# FIT_HDMI_X34-28.net
KiCad netlist of a schematic drawn in Altium Designer
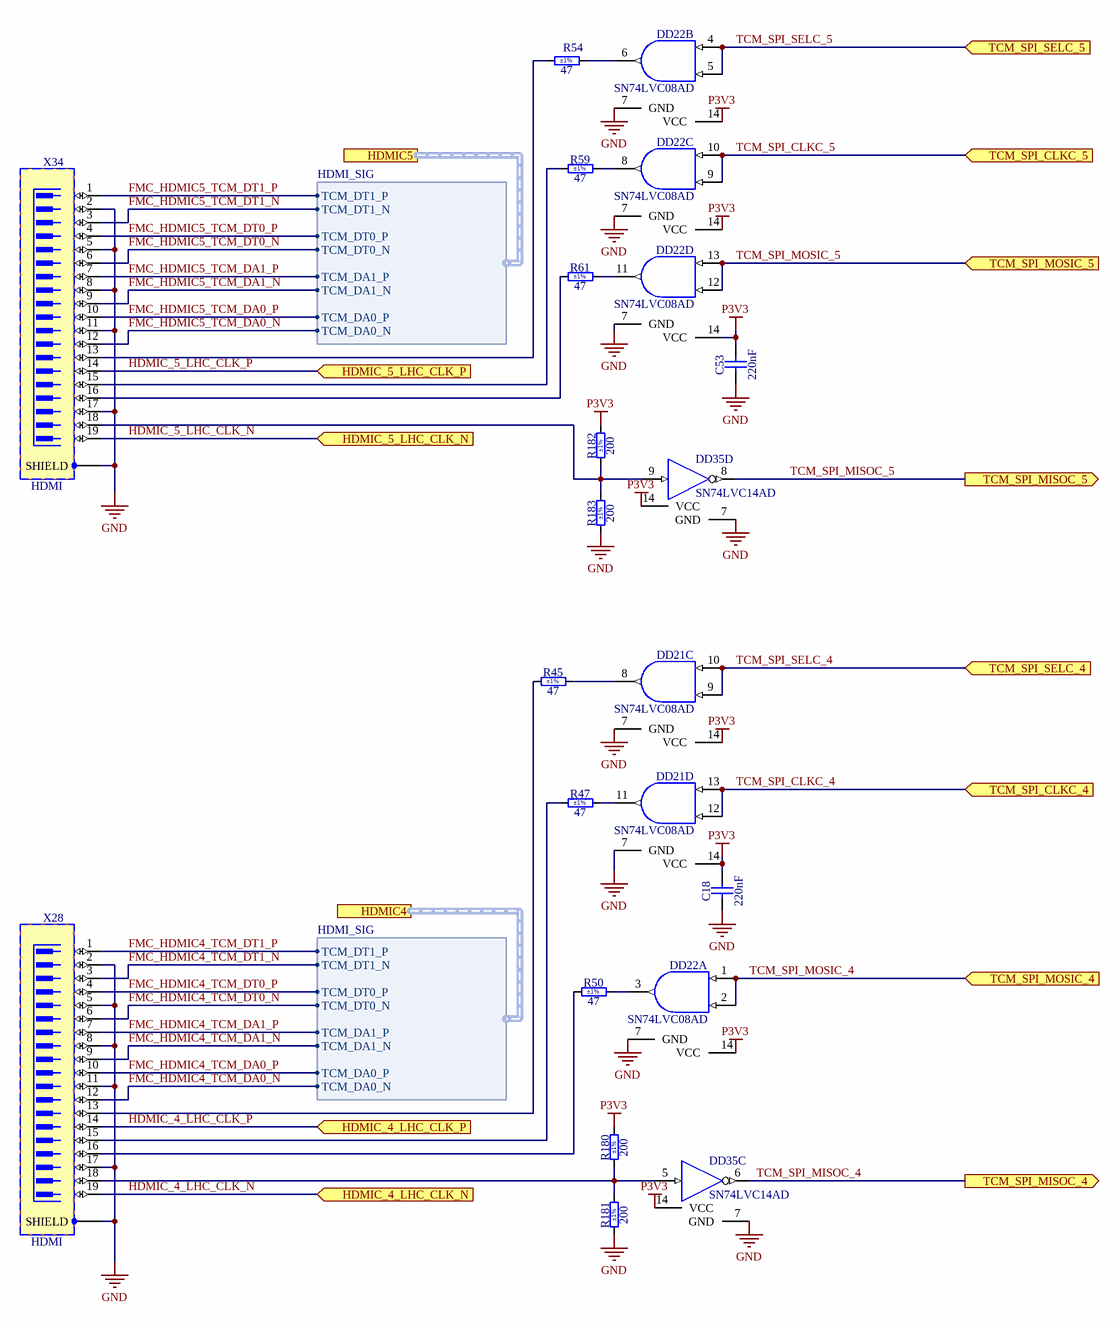
[diagram p0: FIT_HDMI_X34-28.SchDoc]

(export (version "E")
  (design (tool "Eeschema 10.0.6"))
  (components
    (comp (ref "C18")
      (value "220nF")
      (footprint "CAPC2012X135N")
      (description "Non-polarised capacitor")
      (fields
        (field (name "PART NUMBER") "CC0805_220NF_50V_10%_X7R")
        (field (name "VOLTAGE") "50V")
        (field (name "AUTHOR") "CERN DEM JLC")
      )
      (libsource (lib "Capacitors") (part "Capacitor - non polarized"))
    )
    (comp (ref "C53")
      (value "220nF")
      (footprint "CAPC2012X135N")
      (description "Non-polarised capacitor")
      (fields
        (field (name "PART NUMBER") "CC0805_220NF_50V_10%_X7R")
        (field (name "VOLTAGE") "50V")
        (field (name "AUTHOR") "CERN DEM JLC")
      )
      (libsource (lib "Capacitors") (part "Capacitor - non polarized"))
    )
    (comp (ref "DD21")
      (value "SN74LVC08AD")
      (footprint "SOIC127P600X175-14N")
      (description "Quad 2-Input AND Gate")
      (fields (field (name "MANUFACTURER") "TEXAS INSTRUMENTS") (field (name "AUTHOR") "CERN DEM JLC"))
      (libsource (lib "ICs And Semiconductors") (part "7408"))
    )
    (comp (ref "DD22")
      (value "SN74LVC08AD")
      (footprint "SOIC127P600X175-14N")
      (description "Quad 2-Input AND Gate")
      (fields (field (name "MANUFACTURER") "TEXAS INSTRUMENTS") (field (name "AUTHOR") "CERN DEM JLC"))
      (libsource (lib "ICs And Semiconductors") (part "7408"))
    )
    (comp (ref "DD35")
      (value "SN74LVC14AD")
      (footprint "SOIC127P600X175-14N")
      (description "Hex Schmitt-Trigger Inverter")
      (fields (field (name "MANUFACTURER") "TEXAS INSTRUMENTS") (field (name "AUTHOR") "CERN DEM JMW"))
      (libsource (lib "ICs And Semiconductors") (part "7414"))
    )
    (comp (ref "R45")
      (value "47")
      (footprint "RESC2012X60N")
      (description "Resistor - 1%")
      (fields
        (field (name "TOLERANCE") "±1%")
        (field (name "PART NUMBER") "R0805_47R_1%_0.125W_100PPM")
        (field (name "POWER") "0.125W")
        (field (name "AUTHOR") "CERN DEM JLC")
      )
      (libsource (lib "Resistors") (part "Resistor - 1%"))
    )
    (comp (ref "R47")
      (value "47")
      (footprint "RESC2012X60N")
      (description "Resistor - 1%")
      (fields
        (field (name "TOLERANCE") "±1%")
        (field (name "PART NUMBER") "R0805_47R_1%_0.125W_100PPM")
        (field (name "POWER") "0.125W")
        (field (name "AUTHOR") "CERN DEM JLC")
      )
      (libsource (lib "Resistors") (part "Resistor - 1%"))
    )
    (comp (ref "R50")
      (value "47")
      (footprint "RESC2012X60N")
      (description "Resistor - 1%")
      (fields
        (field (name "TOLERANCE") "±1%")
        (field (name "PART NUMBER") "R0805_47R_1%_0.125W_100PPM")
        (field (name "POWER") "0.125W")
        (field (name "AUTHOR") "CERN DEM JLC")
      )
      (libsource (lib "Resistors") (part "Resistor - 1%"))
    )
    (comp (ref "R54")
      (value "47")
      (footprint "RESC2012X60N")
      (description "Resistor - 1%")
      (fields
        (field (name "TOLERANCE") "±1%")
        (field (name "PART NUMBER") "R0805_47R_1%_0.125W_100PPM")
        (field (name "POWER") "0.125W")
        (field (name "AUTHOR") "CERN DEM JLC")
      )
      (libsource (lib "Resistors") (part "Resistor - 1%"))
    )
    (comp (ref "R59")
      (value "47")
      (footprint "RESC2012X60N")
      (description "Resistor - 1%")
      (fields
        (field (name "TOLERANCE") "±1%")
        (field (name "PART NUMBER") "R0805_47R_1%_0.125W_100PPM")
        (field (name "POWER") "0.125W")
        (field (name "AUTHOR") "CERN DEM JLC")
      )
      (libsource (lib "Resistors") (part "Resistor - 1%"))
    )
    (comp (ref "R61")
      (value "47")
      (footprint "RESC2012X60N")
      (description "Resistor - 1%")
      (fields
        (field (name "TOLERANCE") "±1%")
        (field (name "PART NUMBER") "R0805_47R_1%_0.125W_100PPM")
        (field (name "POWER") "0.125W")
        (field (name "AUTHOR") "CERN DEM JLC")
      )
      (libsource (lib "Resistors") (part "Resistor - 1%"))
    )
    (comp (ref "R180")
      (value "200")
      (footprint "RESC2012X60N")
      (description "Resistor - 1%")
      (fields
        (field (name "TOLERANCE") "±1%")
        (field (name "PART NUMBER") "R0805_200R_1%_0.125W_100PPM")
        (field (name "POWER") "0.125W")
        (field (name "AUTHOR") "CERN DEM JLC")
      )
      (libsource (lib "Resistors") (part "Resistor - 1%"))
    )
    (comp (ref "R181")
      (value "200")
      (footprint "RESC2012X60N")
      (description "Resistor - 1%")
      (fields
        (field (name "TOLERANCE") "±1%")
        (field (name "PART NUMBER") "R0805_200R_1%_0.125W_100PPM")
        (field (name "POWER") "0.125W")
        (field (name "AUTHOR") "CERN DEM JLC")
      )
      (libsource (lib "Resistors") (part "Resistor - 1%"))
    )
    (comp (ref "R182")
      (value "200")
      (footprint "RESC2012X60N")
      (description "Resistor - 1%")
      (fields
        (field (name "TOLERANCE") "±1%")
        (field (name "PART NUMBER") "R0805_200R_1%_0.125W_100PPM")
        (field (name "POWER") "0.125W")
        (field (name "AUTHOR") "CERN DEM JLC")
      )
      (libsource (lib "Resistors") (part "Resistor - 1%"))
    )
    (comp (ref "R183")
      (value "200")
      (footprint "RESC2012X60N")
      (description "Resistor - 1%")
      (fields
        (field (name "TOLERANCE") "±1%")
        (field (name "PART NUMBER") "R0805_200R_1%_0.125W_100PPM")
        (field (name "POWER") "0.125W")
        (field (name "AUTHOR") "CERN DEM JLC")
      )
      (libsource (lib "Resistors") (part "Resistor - 1%"))
    )
    (comp (ref "X28")
      (value "HDMI")
      (footprint "TYCO_2007435-1")
      (description "Connector HDMI 19 Male + 1 Shield")
      (fields
        (field (name "PART NUMBER") "TYCO_2007435-1")
        (field (name "MANUFACTURER") "TYCO ELECTRONICS")
        (field (name "AUTHOR") "CERN DEM MR")
      )
      (libsource (lib "Connectors") (part "Connector HDMI 19 Male + 1 Shield"))
    )
    (comp (ref "X34")
      (value "HDMI")
      (footprint "TYCO_2007435-1")
      (description "Connector HDMI 19 Male + 1 Shield")
      (fields
        (field (name "PART NUMBER") "TYCO_2007435-1")
        (field (name "MANUFACTURER") "TYCO ELECTRONICS")
        (field (name "AUTHOR") "CERN DEM MR")
      )
      (libsource (lib "Connectors") (part "Connector HDMI 19 Male + 1 Shield"))
    )
  )
  (nets
    (net (code "2") (name "/FMC_HDMIC4_TCM_DA0_N") (class "Default")
      (node (ref "X28") (pin "12") (pinfunction "12_12") (pintype "bidirectional"))
    )
    (net (code "3") (name "/FMC_HDMIC4_TCM_DA0_P") (class "Default")
      (node (ref "X28") (pin "10") (pinfunction "10_10") (pintype "bidirectional"))
    )
    (net (code "4") (name "/FMC_HDMIC4_TCM_DA1_N") (class "Default")
      (node (ref "X28") (pin "9") (pinfunction "9_9") (pintype "bidirectional"))
    )
    (net (code "5") (name "/FMC_HDMIC4_TCM_DA1_P") (class "Default")
      (node (ref "X28") (pin "7") (pinfunction "7_7") (pintype "bidirectional"))
    )
    (net (code "6") (name "/FMC_HDMIC4_TCM_DT0_N") (class "Default")
      (node (ref "X28") (pin "6") (pinfunction "6_6") (pintype "bidirectional"))
    )
    (net (code "7") (name "/FMC_HDMIC4_TCM_DT0_P") (class "Default")
      (node (ref "X28") (pin "4") (pinfunction "4_4") (pintype "bidirectional"))
    )
    (net (code "8") (name "/FMC_HDMIC4_TCM_DT1_N") (class "Default")
      (node (ref "X28") (pin "3") (pinfunction "3_3") (pintype "bidirectional"))
    )
    (net (code "9") (name "/FMC_HDMIC4_TCM_DT1_P") (class "Default")
      (node (ref "X28") (pin "1") (pinfunction "1_1") (pintype "bidirectional"))
    )
    (net (code "10") (name "/FMC_HDMIC5_TCM_DA0_N") (class "Default")
      (node (ref "X34") (pin "12") (pinfunction "12_12") (pintype "bidirectional"))
    )
    (net (code "11") (name "/FMC_HDMIC5_TCM_DA0_P") (class "Default")
      (node (ref "X34") (pin "10") (pinfunction "10_10") (pintype "bidirectional"))
    )
    (net (code "12") (name "/FMC_HDMIC5_TCM_DA1_N") (class "Default")
      (node (ref "X34") (pin "9") (pinfunction "9_9") (pintype "bidirectional"))
    )
    (net (code "13") (name "/FMC_HDMIC5_TCM_DA1_P") (class "Default")
      (node (ref "X34") (pin "7") (pinfunction "7_7") (pintype "bidirectional"))
    )
    (net (code "14") (name "/FMC_HDMIC5_TCM_DT0_N") (class "Default")
      (node (ref "X34") (pin "6") (pinfunction "6_6") (pintype "bidirectional"))
    )
    (net (code "15") (name "/FMC_HDMIC5_TCM_DT0_P") (class "Default")
      (node (ref "X34") (pin "4") (pinfunction "4_4") (pintype "bidirectional"))
    )
    (net (code "16") (name "/FMC_HDMIC5_TCM_DT1_N") (class "Default")
      (node (ref "X34") (pin "3") (pinfunction "3_3") (pintype "bidirectional"))
    )
    (net (code "17") (name "/FMC_HDMIC5_TCM_DT1_P") (class "Default")
      (node (ref "X34") (pin "1") (pinfunction "1_1") (pintype "bidirectional"))
    )
    (net (code "18") (name "/HDMIC_4_LHC_CLK_N") (class "Default")
      (node (ref "X28") (pin "19") (pinfunction "19_19") (pintype "bidirectional"))
    )
    (net (code "19") (name "/HDMIC_4_LHC_CLK_P") (class "Default")
      (node (ref "X28") (pin "14") (pinfunction "14_14") (pintype "bidirectional"))
    )
    (net (code "20") (name "/HDMIC_5_LHC_CLK_N") (class "Default")
      (node (ref "X34") (pin "19") (pinfunction "19_19") (pintype "bidirectional"))
    )
    (net (code "21") (name "/HDMIC_5_LHC_CLK_P") (class "Default")
      (node (ref "X34") (pin "14") (pinfunction "14_14") (pintype "bidirectional"))
    )
    (net (code "22") (name "/TCM_SPI_CLKC_4") (class "Default")
      (node (ref "DD21") (pin "12") (pinfunction "B_12") (pintype "input"))
      (node (ref "DD21") (pin "13") (pinfunction "A_13") (pintype "input"))
    )
    (net (code "23") (name "/TCM_SPI_CLKC_5") (class "Default")
      (node (ref "DD22") (pin "10") (pinfunction "A_10") (pintype "input"))
      (node (ref "DD22") (pin "9") (pinfunction "B_9") (pintype "input"))
    )
    (net (code "24") (name "/TCM_SPI_MISOC_4") (class "Default")
      (node (ref "DD35") (pin "6") (pinfunction "OUT_6") (pintype "output"))
    )
    (net (code "25") (name "/TCM_SPI_MISOC_5") (class "Default")
      (node (ref "DD35") (pin "8") (pinfunction "OUT_8") (pintype "output"))
    )
    (net (code "26") (name "/TCM_SPI_MOSIC_4") (class "Default")
      (node (ref "DD22") (pin "1") (pinfunction "A_1") (pintype "input"))
      (node (ref "DD22") (pin "2") (pinfunction "B_2") (pintype "input"))
    )
    (net (code "27") (name "/TCM_SPI_MOSIC_5") (class "Default")
      (node (ref "DD22") (pin "12") (pinfunction "B_12") (pintype "input"))
      (node (ref "DD22") (pin "13") (pinfunction "A_13") (pintype "input"))
    )
    (net (code "28") (name "/TCM_SPI_SELC_4") (class "Default")
      (node (ref "DD21") (pin "10") (pinfunction "A_10") (pintype "input"))
      (node (ref "DD21") (pin "9") (pinfunction "B_9") (pintype "input"))
    )
    (net (code "29") (name "/TCM_SPI_SELC_5") (class "Default")
      (node (ref "DD22") (pin "4") (pinfunction "A_4") (pintype "input"))
      (node (ref "DD22") (pin "5") (pinfunction "B_5") (pintype "input"))
    )
    (net (code "31") (name "GND") (class "Default")
      (node (ref "C18") (pin "1") (pinfunction "1_1") (pintype "passive"))
      (node (ref "C53") (pin "1") (pinfunction "1_1") (pintype "passive"))
      (node (ref "DD21") (pin "7") (pinfunction "GND_7") (pintype "power_in"))
      (node (ref "DD22") (pin "7") (pinfunction "GND_7") (pintype "power_in"))
      (node (ref "DD35") (pin "7") (pinfunction "GND_7") (pintype "power_in"))
      (node (ref "R181") (pin "1") (pinfunction "1_1") (pintype "passive"))
      (node (ref "R183") (pin "1") (pinfunction "1_1") (pintype "passive"))
      (node (ref "X28") (pin "11") (pinfunction "11_11") (pintype "bidirectional"))
      (node (ref "X28") (pin "17") (pinfunction "17_17") (pintype "bidirectional"))
      (node (ref "X28") (pin "2") (pinfunction "2_2") (pintype "bidirectional"))
      (node (ref "X28") (pin "5") (pinfunction "5_5") (pintype "bidirectional"))
      (node (ref "X28") (pin "8") (pinfunction "8_8") (pintype "bidirectional"))
      (node (ref "X28") (pin "SHIELD") (pinfunction "SHIELD_SHIELD") (pintype "power_in"))
      (node (ref "X34") (pin "11") (pinfunction "11_11") (pintype "bidirectional"))
      (node (ref "X34") (pin "17") (pinfunction "17_17") (pintype "bidirectional"))
      (node (ref "X34") (pin "2") (pinfunction "2_2") (pintype "bidirectional"))
      (node (ref "X34") (pin "5") (pinfunction "5_5") (pintype "bidirectional"))
      (node (ref "X34") (pin "8") (pinfunction "8_8") (pintype "bidirectional"))
      (node (ref "X34") (pin "SHIELD") (pinfunction "SHIELD_SHIELD") (pintype "power_in"))
    )
    (net (code "32") (name "Net-(DD21C-Y)") (class "Default")
      (node (ref "DD21") (pin "8") (pinfunction "Y_8") (pintype "output"))
      (node (ref "R45") (pin "2") (pinfunction "2_2") (pintype "passive"))
    )
    (net (code "33") (name "Net-(DD21D-Y)") (class "Default")
      (node (ref "DD21") (pin "11") (pinfunction "Y_11") (pintype "output"))
      (node (ref "R47") (pin "2") (pinfunction "2_2") (pintype "passive"))
    )
    (net (code "34") (name "Net-(DD22A-Y)") (class "Default")
      (node (ref "DD22") (pin "3") (pinfunction "Y_3") (pintype "output"))
      (node (ref "R50") (pin "2") (pinfunction "2_2") (pintype "passive"))
    )
    (net (code "35") (name "Net-(DD22B-Y)") (class "Default")
      (node (ref "DD22") (pin "6") (pinfunction "Y_6") (pintype "output"))
      (node (ref "R54") (pin "2") (pinfunction "2_2") (pintype "passive"))
    )
    (net (code "36") (name "Net-(DD22C-Y)") (class "Default")
      (node (ref "DD22") (pin "8") (pinfunction "Y_8") (pintype "output"))
      (node (ref "R59") (pin "2") (pinfunction "2_2") (pintype "passive"))
    )
    (net (code "37") (name "Net-(DD22D-Y)") (class "Default")
      (node (ref "DD22") (pin "11") (pinfunction "Y_11") (pintype "output"))
      (node (ref "R61") (pin "2") (pinfunction "2_2") (pintype "passive"))
    )
    (net (code "38") (name "Net-(DD35C-IN)") (class "Default")
      (node (ref "DD35") (pin "5") (pinfunction "IN_5") (pintype "input"))
      (node (ref "R180") (pin "1") (pinfunction "1_1") (pintype "passive"))
      (node (ref "R181") (pin "2") (pinfunction "2_2") (pintype "passive"))
      (node (ref "X28") (pin "18") (pinfunction "18_18") (pintype "bidirectional"))
    )
    (net (code "39") (name "Net-(DD35D-IN)") (class "Default")
      (node (ref "DD35") (pin "9") (pinfunction "IN_9") (pintype "input"))
      (node (ref "R182") (pin "1") (pinfunction "1_1") (pintype "passive"))
      (node (ref "R183") (pin "2") (pinfunction "2_2") (pintype "passive"))
      (node (ref "X34") (pin "18") (pinfunction "18_18") (pintype "bidirectional"))
    )
    (net (code "40") (name "Net-(R45-Pad1)") (class "Default")
      (node (ref "R45") (pin "1") (pinfunction "1_1") (pintype "passive"))
      (node (ref "X28") (pin "13") (pinfunction "13_13") (pintype "bidirectional"))
    )
    (net (code "41") (name "Net-(R47-Pad1)") (class "Default")
      (node (ref "R47") (pin "1") (pinfunction "1_1") (pintype "passive"))
      (node (ref "X28") (pin "15") (pinfunction "15_15") (pintype "bidirectional"))
    )
    (net (code "42") (name "Net-(R50-Pad1)") (class "Default")
      (node (ref "R50") (pin "1") (pinfunction "1_1") (pintype "passive"))
      (node (ref "X28") (pin "16") (pinfunction "16_16") (pintype "bidirectional"))
    )
    (net (code "43") (name "Net-(R54-Pad1)") (class "Default")
      (node (ref "R54") (pin "1") (pinfunction "1_1") (pintype "passive"))
      (node (ref "X34") (pin "13") (pinfunction "13_13") (pintype "bidirectional"))
    )
    (net (code "44") (name "Net-(R59-Pad1)") (class "Default")
      (node (ref "R59") (pin "1") (pinfunction "1_1") (pintype "passive"))
      (node (ref "X34") (pin "15") (pinfunction "15_15") (pintype "bidirectional"))
    )
    (net (code "45") (name "Net-(R61-Pad1)") (class "Default")
      (node (ref "R61") (pin "1") (pinfunction "1_1") (pintype "passive"))
      (node (ref "X34") (pin "16") (pinfunction "16_16") (pintype "bidirectional"))
    )
    (net (code "46") (name "P3V3") (class "Default")
      (node (ref "C18") (pin "2") (pinfunction "2_2") (pintype "passive"))
      (node (ref "C53") (pin "2") (pinfunction "2_2") (pintype "passive"))
      (node (ref "DD21") (pin "14") (pinfunction "VCC_14") (pintype "power_in"))
      (node (ref "DD22") (pin "14") (pinfunction "VCC_14") (pintype "power_in"))
      (node (ref "DD35") (pin "14") (pinfunction "VCC_14") (pintype "power_in"))
      (node (ref "R180") (pin "2") (pinfunction "2_2") (pintype "passive"))
      (node (ref "R182") (pin "2") (pinfunction "2_2") (pintype "passive"))
    )
  )
)
